# 03_MCU.net
KiCad netlist of a schematic drawn in Altium Designer
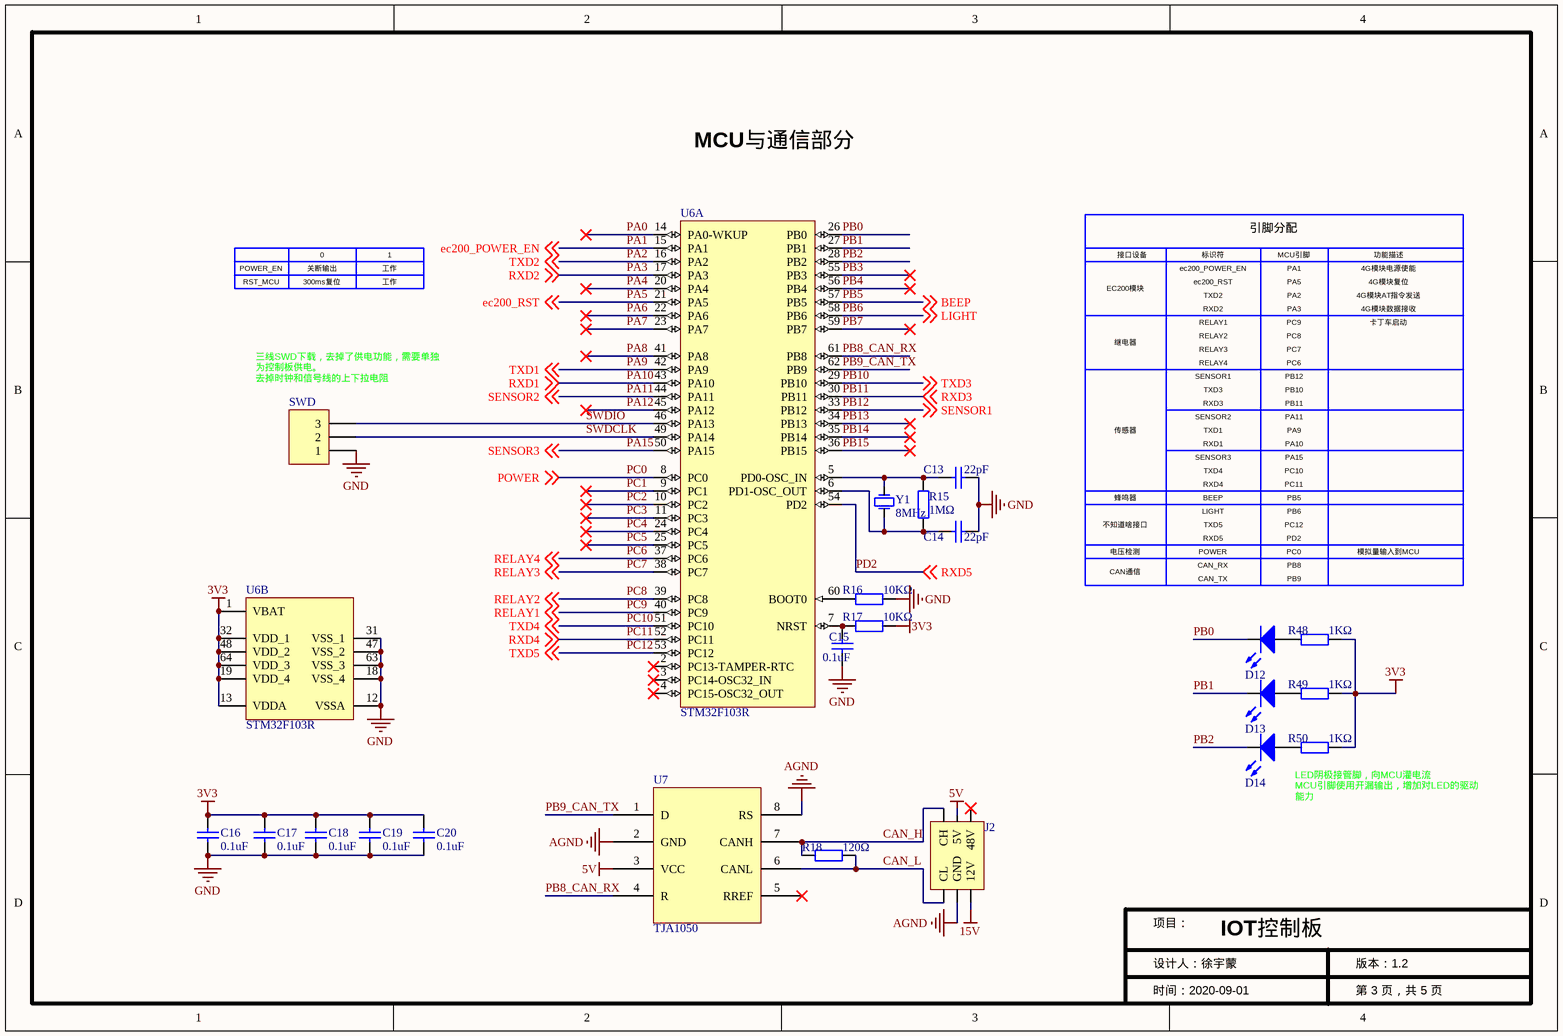
[diagram p0: 03_MCU部分.SchDoc]

(export (version "E")
  (design (tool "Eeschema 10.0.6"))
  (components
    (comp (ref "C13")
      (value "22pF")
      (footprint "CAP-0603")
      (description "无极性电容")
      (fields (field (name "Comment") "Cap") (field (name "PUBLISHER") "Altium Limited"))
      (libsource (lib "Arrowy_Racing") (part "Cap"))
    )
    (comp (ref "C14")
      (value "22pF")
      (footprint "CAP-0603")
      (description "无极性电容")
      (fields (field (name "Comment") "Cap") (field (name "PUBLISHER") "Altium Limited"))
      (libsource (lib "Arrowy_Racing") (part "Cap"))
    )
    (comp (ref "C15")
      (value "0.1uF")
      (footprint "CAP-0603")
      (description "无极性电容")
      (fields (field (name "Comment") "Cap") (field (name "PUBLISHER") "Altium Limited"))
      (libsource (lib "Arrowy_Racing") (part "Cap"))
    )
    (comp (ref "C16")
      (value "0.1uF")
      (footprint "CAP-0603")
      (description "无极性电容")
      (fields (field (name "Comment") "Cap") (field (name "PUBLISHER") "Altium Limited"))
      (libsource (lib "Arrowy_Racing") (part "Cap"))
    )
    (comp (ref "C17")
      (value "0.1uF")
      (footprint "CAP-0603")
      (description "无极性电容")
      (fields (field (name "Comment") "Cap") (field (name "PUBLISHER") "Altium Limited"))
      (libsource (lib "Arrowy_Racing") (part "Cap"))
    )
    (comp (ref "C18")
      (value "0.1uF")
      (footprint "CAP-0603")
      (description "无极性电容")
      (fields (field (name "Comment") "Cap") (field (name "PUBLISHER") "Altium Limited"))
      (libsource (lib "Arrowy_Racing") (part "Cap"))
    )
    (comp (ref "C19")
      (value "0.1uF")
      (footprint "CAP-0603")
      (description "无极性电容")
      (fields (field (name "Comment") "Cap") (field (name "PUBLISHER") "Altium Limited"))
      (libsource (lib "Arrowy_Racing") (part "Cap"))
    )
    (comp (ref "C20")
      (value "0.1uF")
      (footprint "CAP-0603")
      (description "无极性电容")
      (fields (field (name "Comment") "Cap") (field (name "PUBLISHER") "Altium Limited"))
      (libsource (lib "Arrowy_Racing") (part "Cap"))
    )
    (comp (ref "D12")
      (value "LED")
      (footprint "LED_0805")
      (description "发光二极管")
      (fields (field (name "PUBLISHER") "Altium Limited"))
      (libsource (lib "Arrowy_Racing") (part "LED"))
    )
    (comp (ref "D13")
      (value "LED")
      (footprint "LED_0805")
      (description "发光二极管")
      (fields (field (name "PUBLISHER") "Altium Limited"))
      (libsource (lib "Arrowy_Racing") (part "LED"))
    )
    (comp (ref "D14")
      (value "LED")
      (footprint "LED_0805")
      (description "发光二极管")
      (fields (field (name "PUBLISHER") "Altium Limited"))
      (libsource (lib "Arrowy_Racing") (part "LED"))
    )
    (comp (ref "J2") (value "标准接口") (footprint "标准接口-直插-灰色") (libsource (lib "Arrowy_Racing") (part "标准接口")))
    (comp (ref "R15")
      (value "1MΩ")
      (footprint "0603")
      (description "贴片电阻")
      (fields (field (name "Comment") "Res") (field (name "PUBLISHER") "Altium Limited"))
      (libsource (lib "") (part "Res_1"))
    )
    (comp (ref "R16")
      (value "10KΩ")
      (footprint "0603")
      (description "贴片电阻")
      (fields (field (name "Comment") "Res") (field (name "PUBLISHER") "Altium Limited"))
      (libsource (lib "Arrowy_Racing") (part "Res"))
    )
    (comp (ref "R17")
      (value "10KΩ")
      (footprint "0603")
      (description "贴片电阻")
      (fields (field (name "Comment") "Res") (field (name "PUBLISHER") "Altium Limited"))
      (libsource (lib "Arrowy_Racing") (part "Res"))
    )
    (comp (ref "R18")
      (value "120Ω")
      (footprint "0603")
      (description "贴片电阻")
      (fields (field (name "Comment") "Res") (field (name "PUBLISHER") "Altium Limited"))
      (libsource (lib "Arrowy_Racing") (part "Res"))
    )
    (comp (ref "R48")
      (value "1KΩ")
      (footprint "0603")
      (description "贴片电阻")
      (fields (field (name "Comment") "Res") (field (name "PUBLISHER") "Altium Limited"))
      (libsource (lib "Arrowy_Racing") (part "Res"))
    )
    (comp (ref "R49")
      (value "1KΩ")
      (footprint "0603")
      (description "贴片电阻")
      (fields (field (name "Comment") "Res") (field (name "PUBLISHER") "Altium Limited"))
      (libsource (lib "Arrowy_Racing") (part "Res"))
    )
    (comp (ref "R50")
      (value "1KΩ")
      (footprint "0603")
      (description "贴片电阻")
      (fields (field (name "Comment") "Res") (field (name "PUBLISHER") "Altium Limited"))
      (libsource (lib "Arrowy_Racing") (part "Res"))
    )
    (comp (ref "SWD")
      (value "Header3")
      (footprint "Header_3X1_2.54_排针")
      (description "接插件")
      (libsource (lib "Arrowy_Racing") (part "Header3"))
    )
    (comp (ref "U6")
      (value "STM32F103R")
      (footprint "LQFP64")
      (description "STM32单片机64引脚")
      (fields (field (name "PARTNUMBER") "STM32F103RGT6"))
      (libsource (lib "Arrowy_Racing") (part "STM32F103R"))
    )
    (comp (ref "U7")
      (value "TJA1050")
      (footprint "TJA1050")
      (description "CAN收发器芯片")
      (libsource (lib "PCBSchlib_SEU_RobotLab") (part "TJA1050"))
    )
    (comp (ref "Y1")
      (value "8MHz")
      (footprint "X-SM49")
      (description "晶振")
      (fields (field (name "Comment") "XTAL") (field (name "PUBLISHER") "Altium Limited"))
      (libsource (lib "Arrowy_Racing") (part "XTAL"))
    )
  )
  (nets
    (net (code "1") (name "/CAN_H") (class "Default")
      (node (ref "J2") (pin "5") (pinfunction "CH_5") (pintype "passive"))
      (node (ref "R18") (pin "2") (pinfunction "2_2") (pintype "passive"))
      (node (ref "U7") (pin "7") (pinfunction "CANH_7") (pintype "passive"))
    )
    (net (code "2") (name "/CAN_L") (class "Default")
      (node (ref "J2") (pin "6") (pinfunction "CL_6") (pintype "passive"))
      (node (ref "R18") (pin "1") (pinfunction "1_1") (pintype "passive"))
      (node (ref "U7") (pin "6") (pinfunction "CANL_6") (pintype "passive"))
    )
    (net (code "3") (name "/PA0") (class "Default")
      (node (ref "U6") (pin "14") (pinfunction "PA0-WKUP_14") (pintype "bidirectional+no_connect"))
    )
    (net (code "4") (name "/PA4") (class "Default")
      (node (ref "U6") (pin "20") (pinfunction "PA4_20") (pintype "bidirectional+no_connect"))
    )
    (net (code "5") (name "/PA6") (class "Default")
      (node (ref "U6") (pin "22") (pinfunction "PA6_22") (pintype "bidirectional+no_connect"))
    )
    (net (code "6") (name "/PA7") (class "Default")
      (node (ref "U6") (pin "23") (pinfunction "PA7_23") (pintype "bidirectional+no_connect"))
    )
    (net (code "7") (name "/PA8") (class "Default")
      (node (ref "U6") (pin "41") (pinfunction "PA8_41") (pintype "bidirectional+no_connect"))
    )
    (net (code "8") (name "/PA12") (class "Default")
      (node (ref "U6") (pin "45") (pinfunction "PA12_45") (pintype "bidirectional+no_connect"))
    )
    (net (code "9") (name "/PB0") (class "Default")
      (node (ref "D12") (pin "2") (pinfunction "K_2") (pintype "passive"))
      (node (ref "U6") (pin "26") (pinfunction "PB0_26") (pintype "bidirectional"))
    )
    (net (code "10") (name "/PB1") (class "Default")
      (node (ref "D13") (pin "2") (pinfunction "K_2") (pintype "passive"))
      (node (ref "U6") (pin "27") (pinfunction "PB1_27") (pintype "bidirectional"))
    )
    (net (code "11") (name "/PB2") (class "Default")
      (node (ref "D14") (pin "2") (pinfunction "K_2") (pintype "passive"))
      (node (ref "U6") (pin "28") (pinfunction "PB2_28") (pintype "bidirectional"))
    )
    (net (code "12") (name "/PB3") (class "Default")
      (node (ref "U6") (pin "55") (pinfunction "PB3_55") (pintype "bidirectional+no_connect"))
    )
    (net (code "13") (name "/PB4") (class "Default")
      (node (ref "U6") (pin "56") (pinfunction "PB4_56") (pintype "bidirectional+no_connect"))
    )
    (net (code "14") (name "/PB7") (class "Default")
      (node (ref "U6") (pin "59") (pinfunction "PB7_59") (pintype "bidirectional+no_connect"))
    )
    (net (code "15") (name "/PB8_CAN_RX") (class "Default")
      (node (ref "U6") (pin "61") (pinfunction "PB8_61") (pintype "bidirectional"))
      (node (ref "U7") (pin "4") (pinfunction "R_4") (pintype "passive"))
    )
    (net (code "16") (name "/PB9_CAN_TX") (class "Default")
      (node (ref "U6") (pin "62") (pinfunction "PB9_62") (pintype "bidirectional"))
      (node (ref "U7") (pin "1") (pinfunction "D_1") (pintype "passive"))
    )
    (net (code "17") (name "/PB13") (class "Default")
      (node (ref "U6") (pin "34") (pinfunction "PB13_34") (pintype "bidirectional+no_connect"))
    )
    (net (code "18") (name "/PB14") (class "Default")
      (node (ref "U6") (pin "35") (pinfunction "PB14_35") (pintype "bidirectional+no_connect"))
    )
    (net (code "19") (name "/PB15") (class "Default")
      (node (ref "U6") (pin "36") (pinfunction "PB15_36") (pintype "bidirectional+no_connect"))
    )
    (net (code "20") (name "/PC1") (class "Default")
      (node (ref "U6") (pin "9") (pinfunction "PC1_9") (pintype "bidirectional+no_connect"))
    )
    (net (code "21") (name "/PC2") (class "Default")
      (node (ref "U6") (pin "10") (pinfunction "PC2_10") (pintype "bidirectional+no_connect"))
    )
    (net (code "22") (name "/PC3") (class "Default")
      (node (ref "U6") (pin "11") (pinfunction "PC3_11") (pintype "bidirectional+no_connect"))
    )
    (net (code "23") (name "/PC4") (class "Default")
      (node (ref "U6") (pin "24") (pinfunction "PC4_24") (pintype "bidirectional+no_connect"))
    )
    (net (code "24") (name "/PC5") (class "Default")
      (node (ref "U6") (pin "25") (pinfunction "PC5_25") (pintype "bidirectional+no_connect"))
    )
    (net (code "25") (name "/SWDCLK") (class "Default")
      (node (ref "SWD") (pin "2") (pinfunction "2_2") (pintype "passive"))
      (node (ref "U6") (pin "49") (pinfunction "PA14_49") (pintype "bidirectional"))
    )
    (net (code "26") (name "/SWDIO") (class "Default")
      (node (ref "SWD") (pin "3") (pinfunction "3_3") (pintype "passive"))
      (node (ref "U6") (pin "46") (pinfunction "PA13_46") (pintype "bidirectional"))
    )
    (net (code "27") (name "3V3") (class "Default")
      (node (ref "C16") (pin "2") (pinfunction "2_2") (pintype "passive"))
      (node (ref "C17") (pin "2") (pinfunction "2_2") (pintype "passive"))
      (node (ref "C18") (pin "2") (pinfunction "2_2") (pintype "passive"))
      (node (ref "C19") (pin "2") (pinfunction "2_2") (pintype "passive"))
      (node (ref "C20") (pin "2") (pinfunction "2_2") (pintype "passive"))
      (node (ref "R17") (pin "1") (pinfunction "1_1") (pintype "passive"))
      (node (ref "R48") (pin "1") (pinfunction "1_1") (pintype "passive"))
      (node (ref "R49") (pin "1") (pinfunction "1_1") (pintype "passive"))
      (node (ref "R50") (pin "1") (pinfunction "1_1") (pintype "passive"))
      (node (ref "U6") (pin "1") (pinfunction "VBAT_1") (pintype "power_in"))
      (node (ref "U6") (pin "13") (pinfunction "VDDA_13") (pintype "power_in"))
      (node (ref "U6") (pin "19") (pinfunction "VDD_4_19") (pintype "power_in"))
      (node (ref "U6") (pin "32") (pinfunction "VDD_1_32") (pintype "power_in"))
      (node (ref "U6") (pin "48") (pinfunction "VDD_2_48") (pintype "power_in"))
      (node (ref "U6") (pin "64") (pinfunction "VDD_3_64") (pintype "power_in"))
    )
    (net (code "28") (name "5V") (class "Default")
      (node (ref "J2") (pin "3") (pinfunction "5V_3") (pintype "passive"))
      (node (ref "U7") (pin "3") (pinfunction "VCC_3") (pintype "passive"))
    )
    (net (code "29") (name "15V") (class "Default")
      (node (ref "J2") (pin "2") (pinfunction "12V_2") (pintype "passive"))
    )
    (net (code "30") (name "AGND") (class "Default")
      (node (ref "J2") (pin "4") (pinfunction "GND_4") (pintype "passive"))
      (node (ref "U7") (pin "2") (pinfunction "GND_2") (pintype "passive"))
      (node (ref "U7") (pin "8") (pinfunction "RS_8") (pintype "passive"))
    )
    (net (code "31") (name "BEEP") (class "Default")
      (node (ref "U6") (pin "57") (pinfunction "PB5_57") (pintype "bidirectional"))
    )
    (net (code "32") (name "GND") (class "Default")
      (node (ref "C13") (pin "1") (pinfunction "1_1") (pintype "passive"))
      (node (ref "C14") (pin "1") (pinfunction "1_1") (pintype "passive"))
      (node (ref "C15") (pin "1") (pinfunction "1_1") (pintype "passive"))
      (node (ref "C16") (pin "1") (pinfunction "1_1") (pintype "passive"))
      (node (ref "C17") (pin "1") (pinfunction "1_1") (pintype "passive"))
      (node (ref "C18") (pin "1") (pinfunction "1_1") (pintype "passive"))
      (node (ref "C19") (pin "1") (pinfunction "1_1") (pintype "passive"))
      (node (ref "C20") (pin "1") (pinfunction "1_1") (pintype "passive"))
      (node (ref "R16") (pin "1") (pinfunction "1_1") (pintype "passive"))
      (node (ref "SWD") (pin "1") (pinfunction "1_1") (pintype "passive"))
      (node (ref "U6") (pin "12") (pinfunction "VSSA_12") (pintype "power_in"))
      (node (ref "U6") (pin "18") (pinfunction "VSS_4_18") (pintype "power_in"))
      (node (ref "U6") (pin "31") (pinfunction "VSS_1_31") (pintype "power_in"))
      (node (ref "U6") (pin "47") (pinfunction "VSS_2_47") (pintype "power_in"))
      (node (ref "U6") (pin "63") (pinfunction "VSS_3_63") (pintype "power_in"))
    )
    (net (code "33") (name "LIGHT") (class "Default")
      (node (ref "U6") (pin "58") (pinfunction "PB6_58") (pintype "bidirectional"))
    )
    (net (code "34") (name "Net-(D12-A)") (class "Default")
      (node (ref "D12") (pin "1") (pinfunction "A_1") (pintype "passive"))
      (node (ref "R48") (pin "2") (pinfunction "2_2") (pintype "passive"))
    )
    (net (code "35") (name "Net-(D13-A)") (class "Default")
      (node (ref "D13") (pin "1") (pinfunction "A_1") (pintype "passive"))
      (node (ref "R49") (pin "2") (pinfunction "2_2") (pintype "passive"))
    )
    (net (code "36") (name "Net-(D14-A)") (class "Default")
      (node (ref "D14") (pin "1") (pinfunction "A_1") (pintype "passive"))
      (node (ref "R50") (pin "2") (pinfunction "2_2") (pintype "passive"))
    )
    (net (code "37") (name "Net-(U6A-BOOT0)") (class "Default")
      (node (ref "R16") (pin "2") (pinfunction "2_2") (pintype "passive"))
      (node (ref "U6") (pin "60") (pinfunction "BOOT0_60") (pintype "input"))
    )
    (net (code "38") (name "Net-(U6A-NRST)") (class "Default")
      (node (ref "C15") (pin "2") (pinfunction "2_2") (pintype "passive"))
      (node (ref "R17") (pin "2") (pinfunction "2_2") (pintype "passive"))
      (node (ref "U6") (pin "7") (pinfunction "NRST_7") (pintype "bidirectional"))
    )
    (net (code "39") (name "Net-(U6A-PD0-OSC_IN)") (class "Default")
      (node (ref "C13") (pin "2") (pinfunction "2_2") (pintype "passive"))
      (node (ref "R15") (pin "2") (pinfunction "2_2") (pintype "passive"))
      (node (ref "U6") (pin "5") (pinfunction "PD0-OSC_IN_5") (pintype "bidirectional"))
      (node (ref "Y1") (pin "2") (pinfunction "2_2") (pintype "passive"))
    )
    (net (code "40") (name "Net-(U6A-PD1-OSC_OUT)") (class "Default")
      (node (ref "C14") (pin "2") (pinfunction "2_2") (pintype "passive"))
      (node (ref "R15") (pin "1") (pinfunction "1_1") (pintype "passive"))
      (node (ref "U6") (pin "6") (pinfunction "PD1-OSC_OUT_6") (pintype "bidirectional"))
      (node (ref "Y1") (pin "1") (pinfunction "1_1") (pintype "passive"))
    )
    (net (code "41") (name "POWER") (class "Default")
      (node (ref "U6") (pin "8") (pinfunction "PC0_8") (pintype "bidirectional"))
    )
    (net (code "42") (name "RELAY1") (class "Default")
      (node (ref "U6") (pin "40") (pinfunction "PC9_40") (pintype "bidirectional"))
    )
    (net (code "43") (name "RELAY2") (class "Default")
      (node (ref "U6") (pin "39") (pinfunction "PC8_39") (pintype "bidirectional"))
    )
    (net (code "44") (name "RELAY3") (class "Default")
      (node (ref "U6") (pin "38") (pinfunction "PC7_38") (pintype "bidirectional"))
    )
    (net (code "45") (name "RELAY4") (class "Default")
      (node (ref "U6") (pin "37") (pinfunction "PC6_37") (pintype "bidirectional"))
    )
    (net (code "46") (name "RXD1") (class "Default")
      (node (ref "U6") (pin "43") (pinfunction "PA10_43") (pintype "bidirectional"))
    )
    (net (code "47") (name "RXD2") (class "Default")
      (node (ref "U6") (pin "17") (pinfunction "PA3_17") (pintype "bidirectional"))
    )
    (net (code "48") (name "RXD3") (class "Default")
      (node (ref "U6") (pin "30") (pinfunction "PB11_30") (pintype "bidirectional"))
    )
    (net (code "49") (name "RXD4") (class "Default")
      (node (ref "U6") (pin "52") (pinfunction "PC11_52") (pintype "bidirectional"))
    )
    (net (code "50") (name "RXD5") (class "Default")
      (node (ref "U6") (pin "54") (pinfunction "PD2_54") (pintype "bidirectional"))
    )
    (net (code "51") (name "SENSOR1") (class "Default")
      (node (ref "U6") (pin "33") (pinfunction "PB12_33") (pintype "bidirectional"))
    )
    (net (code "52") (name "SENSOR2") (class "Default")
      (node (ref "U6") (pin "44") (pinfunction "PA11_44") (pintype "bidirectional"))
    )
    (net (code "53") (name "SENSOR3") (class "Default")
      (node (ref "U6") (pin "50") (pinfunction "PA15_50") (pintype "bidirectional"))
    )
    (net (code "54") (name "TXD1") (class "Default")
      (node (ref "U6") (pin "42") (pinfunction "PA9_42") (pintype "bidirectional"))
    )
    (net (code "55") (name "TXD2") (class "Default")
      (node (ref "U6") (pin "16") (pinfunction "PA2_16") (pintype "bidirectional"))
    )
    (net (code "56") (name "TXD3") (class "Default")
      (node (ref "U6") (pin "29") (pinfunction "PB10_29") (pintype "bidirectional"))
    )
    (net (code "57") (name "TXD4") (class "Default")
      (node (ref "U6") (pin "51") (pinfunction "PC10_51") (pintype "bidirectional"))
    )
    (net (code "58") (name "TXD5") (class "Default")
      (node (ref "U6") (pin "53") (pinfunction "PC12_53") (pintype "bidirectional"))
    )
    (net (code "59") (name "ec200_POWER_EN") (class "Default")
      (node (ref "U6") (pin "15") (pinfunction "PA1_15") (pintype "bidirectional"))
    )
    (net (code "60") (name "ec200_RST") (class "Default")
      (node (ref "U6") (pin "21") (pinfunction "PA5_21") (pintype "bidirectional"))
    )
    (net (code "61") (name "unconnected-(J2-48V-Pad1)") (class "Default")
      (node (ref "J2") (pin "1") (pinfunction "48V_1") (pintype "passive+no_connect"))
    )
    (net (code "62") (name "unconnected-(U6A-PC13-TAMPER-RTC-Pad2)") (class "Default")
      (node (ref "U6") (pin "2") (pinfunction "PC13-TAMPER-RTC_2") (pintype "bidirectional+no_connect"))
    )
    (net (code "63") (name "unconnected-(U6A-PC14-OSC32_IN-Pad3)") (class "Default")
      (node (ref "U6") (pin "3") (pinfunction "PC14-OSC32_IN_3") (pintype "bidirectional+no_connect"))
    )
    (net (code "64") (name "unconnected-(U6A-PC15-OSC32_OUT-Pad4)") (class "Default")
      (node (ref "U6") (pin "4") (pinfunction "PC15-OSC32_OUT_4") (pintype "bidirectional+no_connect"))
    )
    (net (code "65") (name "unconnected-(U7-RREF-Pad5)") (class "Default")
      (node (ref "U7") (pin "5") (pinfunction "RREF_5") (pintype "passive+no_connect"))
    )
  )
)
